# Un_51_old.net
KiCad netlist of a schematic drawn in EAGLE
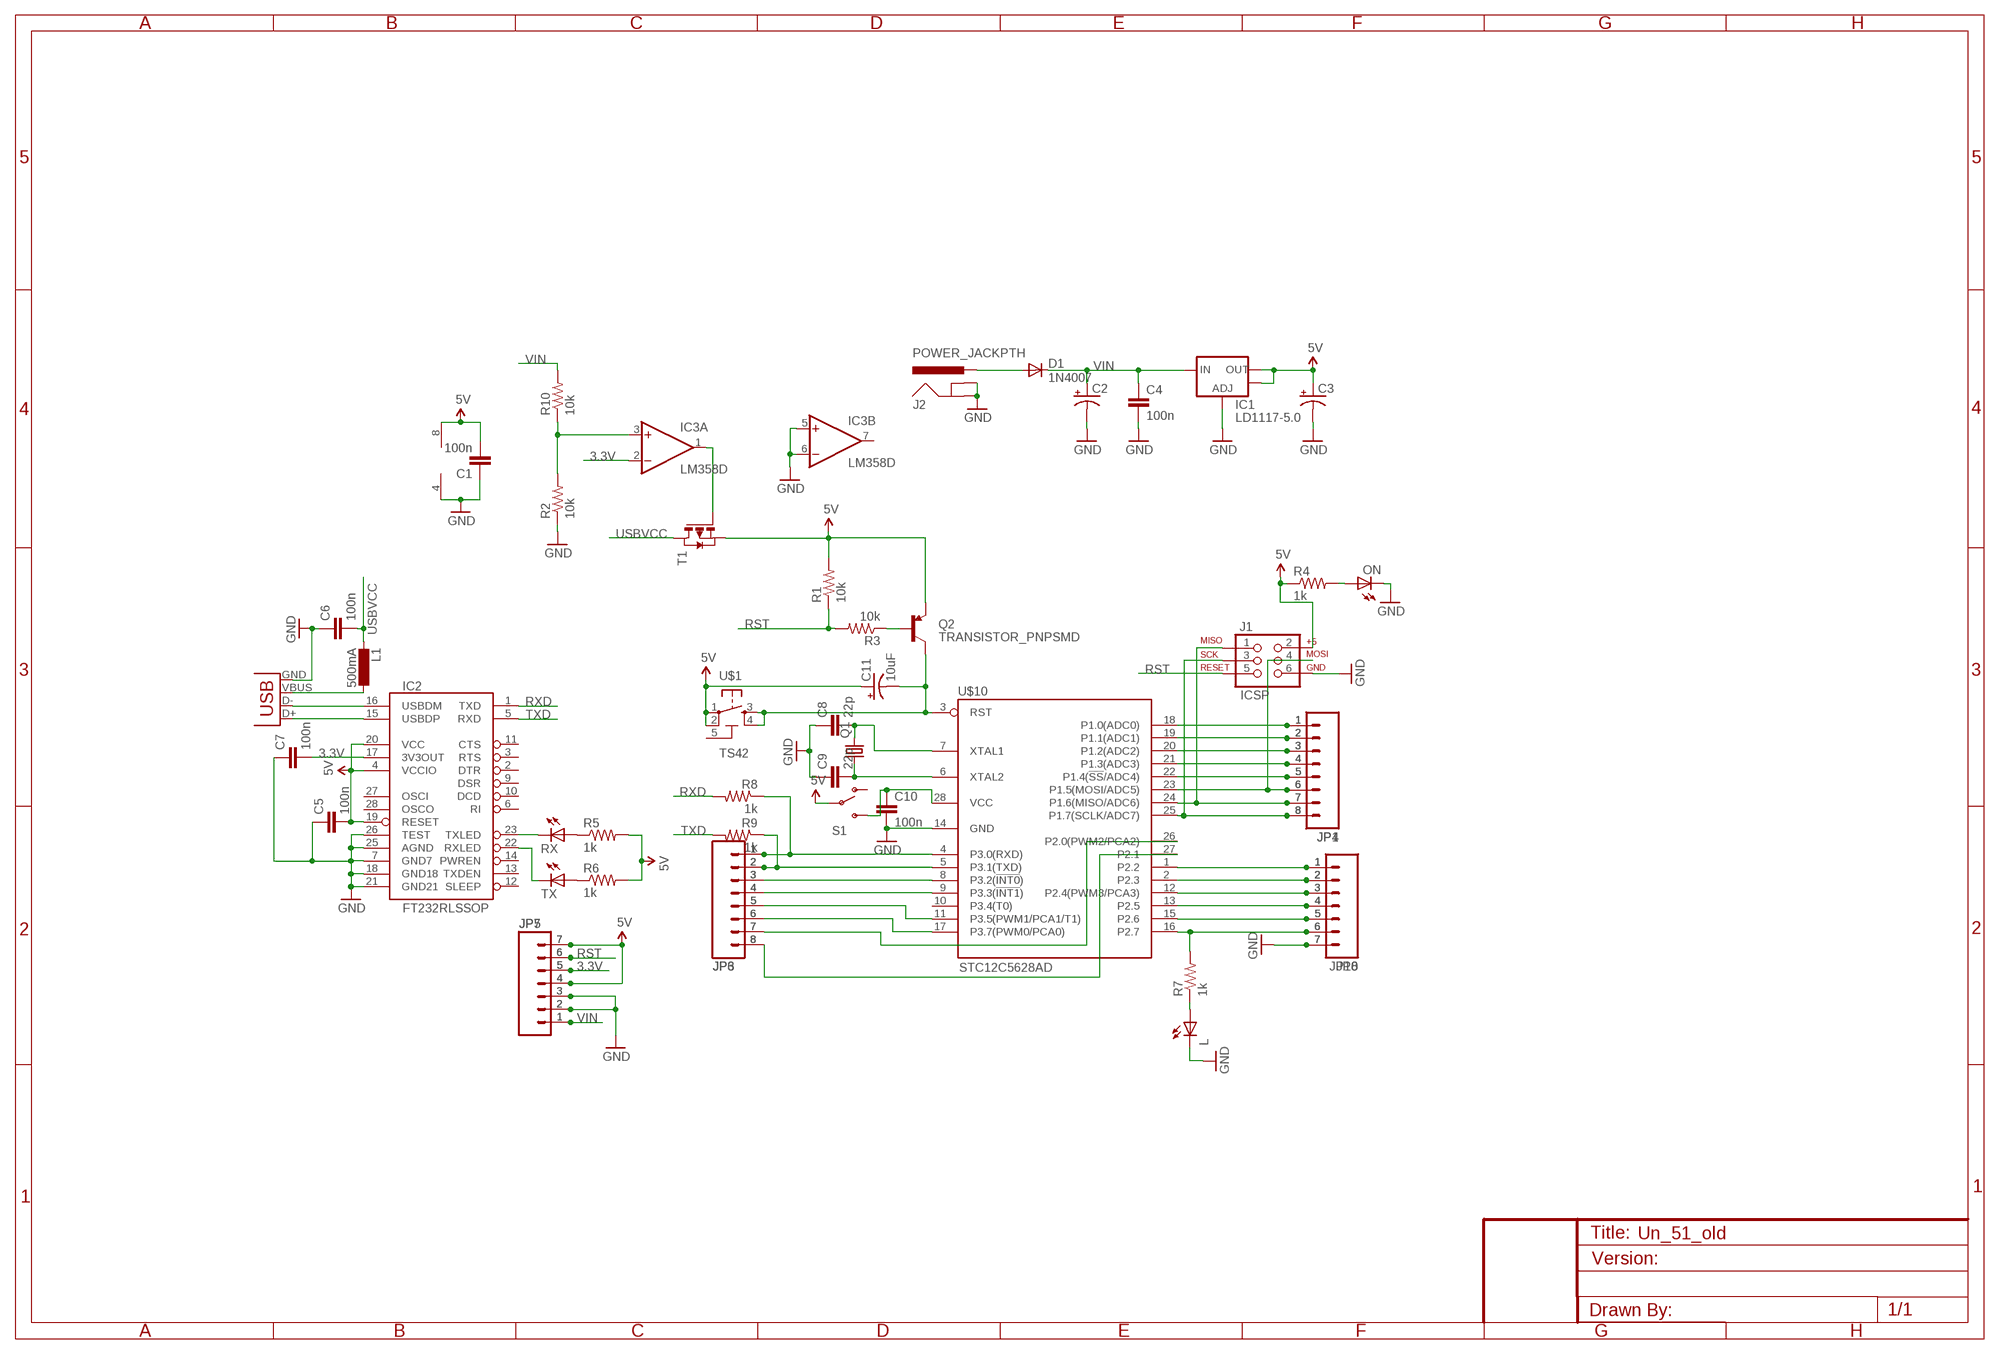
[diagram p0: schematic, sheet 1]

(export (version "E")
  (design (tool "Eeschema 10.0.6"))
  (components
    (comp (ref "C1")
      (value "100n")
      (footprint "eagle-import:0603-CAP")
      (libsource (lib "eagle-import") (part "CAP0603-CAP"))
    )
    (comp (ref "C2")
      (value "CAP_POLD")
      (footprint "eagle-import:PANASONIC_D")
      (libsource (lib "eagle-import") (part "CAP_POLD"))
    )
    (comp (ref "C3")
      (value "CAP_POLD")
      (footprint "eagle-import:PANASONIC_D")
      (libsource (lib "eagle-import") (part "CAP_POLD"))
    )
    (comp (ref "C4")
      (value "100n")
      (footprint "eagle-import:0603-CAP")
      (libsource (lib "eagle-import") (part "CAP0603-CAP"))
    )
    (comp (ref "C5")
      (value "100n")
      (footprint "eagle-import:0603-CAP")
      (libsource (lib "eagle-import") (part "CAP0603-CAP"))
    )
    (comp (ref "C6")
      (value "100n")
      (footprint "eagle-import:0603-CAP")
      (libsource (lib "eagle-import") (part "CAP0603-CAP"))
    )
    (comp (ref "C7")
      (value "100n")
      (footprint "eagle-import:0603-CAP")
      (libsource (lib "eagle-import") (part "CAP0603-CAP"))
    )
    (comp (ref "C8")
      (value "22p")
      (footprint "eagle-import:0805")
      (libsource (lib "eagle-import") (part "CAP0805"))
    )
    (comp (ref "C9")
      (value "22p")
      (footprint "eagle-import:0805")
      (libsource (lib "eagle-import") (part "CAP0805"))
    )
    (comp (ref "C10")
      (value "100n")
      (footprint "eagle-import:0603-CAP")
      (libsource (lib "eagle-import") (part "CAP0603-CAP"))
    )
    (comp (ref "C11")
      (value "10uF")
      (footprint "eagle-import:EIA3216")
      (libsource (lib "eagle-import") (part "CAP_POL1206"))
    )
    (comp (ref "D1")
      (value "1N4007")
      (footprint "eagle-import:SMB")
      (libsource (lib "eagle-import") (part "DIODE-SMB"))
    )
    (comp (ref "IC1")
      (value "LD1117-5.0")
      (footprint "eagle-import:SOT223")
      (libsource (lib "eagle-import") (part "V_REG_LM1117SOT223"))
    )
    (comp (ref "IC2")
      (value "FT232RLSSOP")
      (footprint "eagle-import:SSOP28DB")
      (libsource (lib "eagle-import") (part "FT232RLSSOP"))
    )
    (comp (ref "IC3")
      (value "LM358D")
      (footprint "eagle-import:SO08")
      (libsource (lib "eagle-import") (part "LM358D"))
    )
    (comp (ref "J1")
      (value "ICSP")
      (footprint "eagle-import:2X3")
      (libsource (lib "eagle-import") (part "AVR_SPI_PRG_6PTH"))
    )
    (comp (ref "J2")
      (value "POWER_JACKPTH")
      (footprint "eagle-import:POWER_JACK_PTH")
      (libsource (lib "eagle-import") (part "POWER_JACKPTH"))
    )
    (comp (ref "JP1")
      (value "M081X08")
      (footprint "eagle-import:1X08")
      (libsource (lib "eagle-import") (part "M081X08"))
    )
    (comp (ref "JP3")
      (value "M08")
      (footprint "eagle-import:1X08")
      (libsource (lib "eagle-import") (part "M08"))
    )
    (comp (ref "JP4")
      (value "M081X08")
      (footprint "eagle-import:1X08")
      (libsource (lib "eagle-import") (part "M081X08"))
    )
    (comp (ref "JP5")
      (value "M07")
      (footprint "eagle-import:1X07")
      (libsource (lib "eagle-import") (part "M07"))
    )
    (comp (ref "JP6")
      (value "M08")
      (footprint "eagle-import:1X08")
      (libsource (lib "eagle-import") (part "M08"))
    )
    (comp (ref "JP7")
      (value "M07")
      (footprint "eagle-import:1X07")
      (libsource (lib "eagle-import") (part "M07"))
    )
    (comp (ref "JP8")
      (value "M07")
      (footprint "eagle-import:1X07")
      (libsource (lib "eagle-import") (part "M07"))
    )
    (comp (ref "JP10")
      (value "M07")
      (footprint "eagle-import:1X07")
      (libsource (lib "eagle-import") (part "M07"))
    )
    (comp (ref "L")
      (value "LED0805")
      (footprint "eagle-import:LED-0805")
      (libsource (lib "eagle-import") (part "LED0805"))
    )
    (comp (ref "L1")
      (value "500mA")
      (footprint "eagle-import:L1812")
      (libsource (lib "eagle-import") (part "L-EUL1812"))
    )
    (comp (ref "ON")
      (value "LED0805")
      (footprint "eagle-import:LED-0805")
      (libsource (lib "eagle-import") (part "LED0805"))
    )
    (comp (ref "Q1")
      (value "CRYSTALHC49US")
      (footprint "eagle-import:HC49US")
      (libsource (lib "eagle-import") (part "CRYSTALHC49US"))
    )
    (comp (ref "Q2")
      (value "TRANSISTOR_PNPSMD")
      (footprint "eagle-import:SOT23-3")
      (libsource (lib "eagle-import") (part "TRANSISTOR_PNPSMD"))
    )
    (comp (ref "R1")
      (value "10k")
      (footprint "eagle-import:0805")
      (libsource (lib "eagle-import") (part "RESISTOR0805-RES"))
    )
    (comp (ref "R2")
      (value "10k")
      (footprint "eagle-import:0805")
      (libsource (lib "eagle-import") (part "RESISTOR0805-RES"))
    )
    (comp (ref "R3")
      (value "10k")
      (footprint "eagle-import:0805")
      (libsource (lib "eagle-import") (part "RESISTOR0805-RES"))
    )
    (comp (ref "R4")
      (value "1k")
      (footprint "eagle-import:0805")
      (libsource (lib "eagle-import") (part "RESISTOR0805-RES"))
    )
    (comp (ref "R5")
      (value "1k")
      (footprint "eagle-import:0805")
      (libsource (lib "eagle-import") (part "RESISTOR0805-RES"))
    )
    (comp (ref "R6")
      (value "1k")
      (footprint "eagle-import:0805")
      (libsource (lib "eagle-import") (part "RESISTOR0805-RES"))
    )
    (comp (ref "R7")
      (value "1k")
      (footprint "eagle-import:0805")
      (libsource (lib "eagle-import") (part "RESISTOR0805-RES"))
    )
    (comp (ref "R8")
      (value "1k")
      (footprint "eagle-import:0805")
      (libsource (lib "eagle-import") (part "RESISTOR0805-RES"))
    )
    (comp (ref "R9")
      (value "1k")
      (footprint "eagle-import:0805")
      (libsource (lib "eagle-import") (part "RESISTOR0805-RES"))
    )
    (comp (ref "R10")
      (value "10k")
      (footprint "eagle-import:0805")
      (libsource (lib "eagle-import") (part "RESISTOR0805-RES"))
    )
    (comp (ref "RX")
      (value "LED0805")
      (footprint "eagle-import:LED-0805")
      (libsource (lib "eagle-import") (part "LED0805"))
    )
    (comp (ref "S1")
      (value "SWITCH-SPST")
      (footprint "eagle-import:SWITCH-SPDT2")
      (libsource (lib "eagle-import") (part "SWITCH-SPST"))
    )
    (comp (ref "T1")
      (value "PMOSSOT23")
      (footprint "eagle-import:SOT-23")
      (libsource (lib "eagle-import") (part "PMOSSOT23"))
    )
    (comp (ref "TX")
      (value "LED0805")
      (footprint "eagle-import:LED-0805")
      (libsource (lib "eagle-import") (part "LED0805"))
    )
    (comp (ref "U$1")
      (value "TS42")
      (footprint "eagle-import:TS42")
      (libsource (lib "eagle-import") (part "TS42"))
    )
    (comp (ref "U$10")
      (value "STC12C5628AD")
      (footprint "eagle-import:SO-28W")
      (libsource (lib "eagle-import") (part "STC12C5628AD"))
    )
    (comp (ref "X1")
      (value "USBPTH")
      (footprint "eagle-import:USB-B-PTH")
      (libsource (lib "eagle-import") (part "USBPTH"))
    )
  )
  (nets
    (net (code "1") (name "/3.3V") (class "Default")
      (node (ref "C7") (pin "2") (pinfunction "2_2") (pintype "passive"))
      (node (ref "IC2") (pin "17") (pinfunction "3V3OUT_17") (pintype "output"))
      (node (ref "IC3") (pin "2") (pinfunction "-IN_2") (pintype "input"))
      (node (ref "JP5") (pin "5") (pinfunction "5_5") (pintype "passive"))
      (node (ref "JP7") (pin "5") (pinfunction "5_5") (pintype "passive"))
    )
    (net (code "2") (name "/RST") (class "Default")
      (node (ref "J1") (pin "5") (pinfunction "5_5") (pintype "passive"))
      (node (ref "JP5") (pin "6") (pinfunction "6_6") (pintype "passive"))
      (node (ref "JP7") (pin "6") (pinfunction "6_6") (pintype "passive"))
      (node (ref "R1") (pin "1") (pinfunction "1_1") (pintype "passive"))
      (node (ref "R3") (pin "2") (pinfunction "2_2") (pintype "passive"))
    )
    (net (code "3") (name "/RXD") (class "Default")
      (node (ref "IC2") (pin "1") (pinfunction "TXD_1") (pintype "output"))
      (node (ref "R8") (pin "2") (pinfunction "2_2") (pintype "passive"))
    )
    (net (code "4") (name "/TXD") (class "Default")
      (node (ref "IC2") (pin "5") (pinfunction "RXD_5") (pintype "input"))
      (node (ref "R9") (pin "2") (pinfunction "2_2") (pintype "passive"))
    )
    (net (code "5") (name "/USBVCC") (class "Default")
      (node (ref "C6") (pin "2") (pinfunction "2_2") (pintype "passive"))
      (node (ref "L1") (pin "2") (pinfunction "2_2") (pintype "passive"))
      (node (ref "T1") (pin "1") (pinfunction "D_1") (pintype "passive"))
    )
    (net (code "6") (name "/VIN") (class "Default")
      (node (ref "C2") (pin "+") (pinfunction "+_+") (pintype "passive"))
      (node (ref "C4") (pin "1") (pinfunction "1_1") (pintype "passive"))
      (node (ref "D1") (pin "C") (pinfunction "C_C") (pintype "passive"))
      (node (ref "IC1") (pin "3") (pinfunction "IN_3") (pintype "input"))
      (node (ref "JP5") (pin "1") (pinfunction "1_1") (pintype "passive"))
      (node (ref "JP7") (pin "1") (pinfunction "1_1") (pintype "passive"))
      (node (ref "R10") (pin "2") (pinfunction "2_2") (pintype "passive"))
    )
    (net (code "7") (name "5V") (class "Default")
      (node (ref "C1") (pin "2") (pinfunction "2_2") (pintype "passive"))
      (node (ref "C11") (pin "A") (pinfunction "+_A") (pintype "passive"))
      (node (ref "C3") (pin "+") (pinfunction "+_+") (pintype "passive"))
      (node (ref "C5") (pin "2") (pinfunction "2_2") (pintype "passive"))
      (node (ref "IC1") (pin "2") (pinfunction "OUT_2") (pintype "output"))
      (node (ref "IC1") (pin "4") (pinfunction "OUT_4") (pintype "output"))
      (node (ref "IC2") (pin "19") (pinfunction "RESET_19") (pintype "input"))
      (node (ref "IC2") (pin "20") (pinfunction "VCC_20") (pintype "power_in"))
      (node (ref "IC2") (pin "4") (pinfunction "VCCIO_4") (pintype "power_in"))
      (node (ref "IC3") (pin "8") (pinfunction "V+_8") (pintype "power_in"))
      (node (ref "J1") (pin "2") (pinfunction "2_2") (pintype "passive"))
      (node (ref "JP5") (pin "4") (pinfunction "4_4") (pintype "passive"))
      (node (ref "JP5") (pin "7") (pinfunction "7_7") (pintype "passive"))
      (node (ref "JP7") (pin "4") (pinfunction "4_4") (pintype "passive"))
      (node (ref "JP7") (pin "7") (pinfunction "7_7") (pintype "passive"))
      (node (ref "Q2") (pin "2") (pinfunction "E_2") (pintype "passive"))
      (node (ref "R1") (pin "2") (pinfunction "2_2") (pintype "passive"))
      (node (ref "R4") (pin "1") (pinfunction "1_1") (pintype "passive"))
      (node (ref "R5") (pin "2") (pinfunction "2_2") (pintype "passive"))
      (node (ref "R6") (pin "2") (pinfunction "2_2") (pintype "passive"))
      (node (ref "S1") (pin "2") (pinfunction "P_2") (pintype "passive"))
      (node (ref "T1") (pin "2") (pinfunction "S_2") (pintype "passive"))
      (node (ref "U$1") (pin "1") (pinfunction "1_1") (pintype "passive"))
      (node (ref "U$1") (pin "2") (pinfunction "2_2") (pintype "passive"))
    )
    (net (code "8") (name "GND") (class "Default")
      (node (ref "C1") (pin "1") (pinfunction "1_1") (pintype "passive"))
      (node (ref "C10") (pin "2") (pinfunction "2_2") (pintype "passive"))
      (node (ref "C2") (pin "-") (pinfunction "-_-") (pintype "passive"))
      (node (ref "C3") (pin "-") (pinfunction "-_-") (pintype "passive"))
      (node (ref "C4") (pin "2") (pinfunction "2_2") (pintype "passive"))
      (node (ref "C5") (pin "1") (pinfunction "1_1") (pintype "passive"))
      (node (ref "C6") (pin "1") (pinfunction "1_1") (pintype "passive"))
      (node (ref "C7") (pin "1") (pinfunction "1_1") (pintype "passive"))
      (node (ref "C8") (pin "1") (pinfunction "1_1") (pintype "passive"))
      (node (ref "C9") (pin "1") (pinfunction "1_1") (pintype "passive"))
      (node (ref "IC1") (pin "1") (pinfunction "ADJ_1") (pintype "input"))
      (node (ref "IC2") (pin "18") (pinfunction "GND18_18") (pintype "power_in"))
      (node (ref "IC2") (pin "21") (pinfunction "GND21_21") (pintype "power_in"))
      (node (ref "IC2") (pin "25") (pinfunction "AGND_25") (pintype "power_in"))
      (node (ref "IC2") (pin "26") (pinfunction "TEST_26") (pintype "input"))
      (node (ref "IC2") (pin "7") (pinfunction "GND7_7") (pintype "power_in"))
      (node (ref "IC3") (pin "4") (pinfunction "V-_4") (pintype "power_in"))
      (node (ref "IC3") (pin "5") (pinfunction "+IN_5") (pintype "input"))
      (node (ref "IC3") (pin "6") (pinfunction "-IN_6") (pintype "input"))
      (node (ref "J1") (pin "6") (pinfunction "6_6") (pintype "passive"))
      (node (ref "J2") (pin "GND") (pinfunction "GND_GND") (pintype "bidirectional"))
      (node (ref "J2") (pin "GNDBREAK") (pinfunction "GNDBREAK_GNDBREAK") (pintype "bidirectional"))
      (node (ref "JP10") (pin "7") (pinfunction "7_7") (pintype "passive"))
      (node (ref "JP5") (pin "2") (pinfunction "2_2") (pintype "passive"))
      (node (ref "JP5") (pin "3") (pinfunction "3_3") (pintype "passive"))
      (node (ref "JP7") (pin "2") (pinfunction "2_2") (pintype "passive"))
      (node (ref "JP7") (pin "3") (pinfunction "3_3") (pintype "passive"))
      (node (ref "JP8") (pin "7") (pinfunction "7_7") (pintype "passive"))
      (node (ref "L") (pin "2") (pinfunction "C_2") (pintype "passive"))
      (node (ref "ON") (pin "2") (pinfunction "C_2") (pintype "passive"))
      (node (ref "R2") (pin "1") (pinfunction "1_1") (pintype "passive"))
      (node (ref "U$10") (pin "14") (pinfunction "GND_14") (pintype "bidirectional"))
      (node (ref "X1") (pin "GND") (pinfunction "GND_GND") (pintype "bidirectional"))
    )
    (net (code "9") (name "Net-(C11--)") (class "Default")
      (node (ref "C11") (pin "C") (pinfunction "-_C") (pintype "passive"))
      (node (ref "Q2") (pin "3") (pinfunction "C_3") (pintype "passive"))
      (node (ref "U$1") (pin "3") (pinfunction "3_3") (pintype "passive"))
      (node (ref "U$1") (pin "4") (pinfunction "4_4") (pintype "passive"))
      (node (ref "U$10") (pin "3") (pinfunction "RST_3") (pintype "bidirectional"))
    )
    (net (code "10") (name "Net-(D1-PadA)") (class "Default")
      (node (ref "D1") (pin "A") (pinfunction "A_A") (pintype "passive"))
      (node (ref "J2") (pin "PWR") (pinfunction "PWR_PWR") (pintype "bidirectional"))
    )
    (net (code "11") (name "Net-(IC2-RXLED)") (class "Default")
      (node (ref "IC2") (pin "22") (pinfunction "RXLED_22") (pintype "input"))
      (node (ref "TX") (pin "2") (pinfunction "C_2") (pintype "passive"))
    )
    (net (code "12") (name "Net-(IC2-TXLED)") (class "Default")
      (node (ref "IC2") (pin "23") (pinfunction "TXLED_23") (pintype "input"))
      (node (ref "RX") (pin "2") (pinfunction "C_2") (pintype "passive"))
    )
    (net (code "13") (name "Net-(IC2-USBDM)") (class "Default")
      (node (ref "IC2") (pin "16") (pinfunction "USBDM_16") (pintype "bidirectional"))
      (node (ref "X1") (pin "D-") (pinfunction "D-_D-") (pintype "bidirectional"))
    )
    (net (code "14") (name "Net-(IC2-USBDP)") (class "Default")
      (node (ref "IC2") (pin "15") (pinfunction "USBDP_15") (pintype "bidirectional"))
      (node (ref "X1") (pin "D+") (pinfunction "D+_D+") (pintype "bidirectional"))
    )
    (net (code "15") (name "Net-(IC3A-+IN)") (class "Default")
      (node (ref "IC3") (pin "3") (pinfunction "+IN_3") (pintype "input"))
      (node (ref "R10") (pin "1") (pinfunction "1_1") (pintype "passive"))
      (node (ref "R2") (pin "2") (pinfunction "2_2") (pintype "passive"))
    )
    (net (code "16") (name "Net-(IC3A-OUT)") (class "Default")
      (node (ref "IC3") (pin "1") (pinfunction "OUT_1") (pintype "output"))
      (node (ref "T1") (pin "3") (pinfunction "G_3") (pintype "passive"))
    )
    (net (code "17") (name "Net-(L-A)") (class "Default")
      (node (ref "L") (pin "1") (pinfunction "A_1") (pintype "passive"))
      (node (ref "R7") (pin "1") (pinfunction "1_1") (pintype "passive"))
    )
    (net (code "18") (name "Net-(L1-Pad1)") (class "Default")
      (node (ref "L1") (pin "1") (pinfunction "1_1") (pintype "passive"))
      (node (ref "X1") (pin "VBUS") (pinfunction "VBUS_VBUS") (pintype "bidirectional"))
    )
    (net (code "19") (name "Net-(ON-A)") (class "Default")
      (node (ref "ON") (pin "1") (pinfunction "A_1") (pintype "passive"))
      (node (ref "R4") (pin "2") (pinfunction "2_2") (pintype "passive"))
    )
    (net (code "20") (name "Net-(Q2-B)") (class "Default")
      (node (ref "Q2") (pin "1") (pinfunction "B_1") (pintype "passive"))
      (node (ref "R3") (pin "1") (pinfunction "1_1") (pintype "passive"))
    )
    (net (code "21") (name "Net-(RX-A)") (class "Default")
      (node (ref "R5") (pin "1") (pinfunction "1_1") (pintype "passive"))
      (node (ref "RX") (pin "1") (pinfunction "A_1") (pintype "passive"))
    )
    (net (code "22") (name "Net-(S1-S)") (class "Default")
      (node (ref "C10") (pin "1") (pinfunction "1_1") (pintype "passive"))
      (node (ref "S1") (pin "3") (pinfunction "S_3") (pintype "passive"))
      (node (ref "U$10") (pin "28") (pinfunction "VCC_28") (pintype "bidirectional"))
    )
    (net (code "23") (name "Net-(TX-A)") (class "Default")
      (node (ref "R6") (pin "1") (pinfunction "1_1") (pintype "passive"))
      (node (ref "TX") (pin "1") (pinfunction "A_1") (pintype "passive"))
    )
    (net (code "24") (name "Net-(U$10-P1.0(ADC0))") (class "Default")
      (node (ref "JP1") (pin "1") (pinfunction "1_1") (pintype "passive"))
      (node (ref "JP4") (pin "1") (pinfunction "1_1") (pintype "passive"))
      (node (ref "U$10") (pin "18") (pinfunction "P1.0(ADC0)_18") (pintype "bidirectional"))
    )
    (net (code "25") (name "Net-(U$10-P1.1(ADC1))") (class "Default")
      (node (ref "JP1") (pin "2") (pinfunction "2_2") (pintype "passive"))
      (node (ref "JP4") (pin "2") (pinfunction "2_2") (pintype "passive"))
      (node (ref "U$10") (pin "19") (pinfunction "P1.1(ADC1)_19") (pintype "bidirectional"))
    )
    (net (code "26") (name "Net-(U$10-P1.2(ADC2))") (class "Default")
      (node (ref "JP1") (pin "3") (pinfunction "3_3") (pintype "passive"))
      (node (ref "JP4") (pin "3") (pinfunction "3_3") (pintype "passive"))
      (node (ref "U$10") (pin "20") (pinfunction "P1.2(ADC2)_20") (pintype "bidirectional"))
    )
    (net (code "27") (name "Net-(U$10-P1.3(ADC3))") (class "Default")
      (node (ref "JP1") (pin "4") (pinfunction "4_4") (pintype "passive"))
      (node (ref "JP4") (pin "4") (pinfunction "4_4") (pintype "passive"))
      (node (ref "U$10") (pin "21") (pinfunction "P1.3(ADC3)_21") (pintype "bidirectional"))
    )
    (net (code "28") (name "Net-(U$10-P1.4(~{SS}{slash}ADC4))") (class "Default")
      (node (ref "JP1") (pin "5") (pinfunction "5_5") (pintype "passive"))
      (node (ref "JP4") (pin "5") (pinfunction "5_5") (pintype "passive"))
      (node (ref "U$10") (pin "22") (pinfunction "P1.4(~{SS}/ADC4)_22") (pintype "bidirectional"))
    )
    (net (code "29") (name "Net-(U$10-P1.5(MOSI{slash}ADC5))") (class "Default")
      (node (ref "J1") (pin "4") (pinfunction "4_4") (pintype "passive"))
      (node (ref "JP1") (pin "6") (pinfunction "6_6") (pintype "passive"))
      (node (ref "JP4") (pin "6") (pinfunction "6_6") (pintype "passive"))
      (node (ref "U$10") (pin "23") (pinfunction "P1.5(MOSI/ADC5)_23") (pintype "bidirectional"))
    )
    (net (code "30") (name "Net-(U$10-P1.6(MISO{slash}ADC6))") (class "Default")
      (node (ref "J1") (pin "1") (pinfunction "1_1") (pintype "passive"))
      (node (ref "JP1") (pin "7") (pinfunction "7_7") (pintype "passive"))
      (node (ref "JP4") (pin "7") (pinfunction "7_7") (pintype "passive"))
      (node (ref "U$10") (pin "24") (pinfunction "P1.6(MISO/ADC6)_24") (pintype "bidirectional"))
    )
    (net (code "31") (name "Net-(U$10-P1.7(SCLK{slash}ADC7))") (class "Default")
      (node (ref "J1") (pin "3") (pinfunction "3_3") (pintype "passive"))
      (node (ref "JP1") (pin "8") (pinfunction "8_8") (pintype "passive"))
      (node (ref "JP4") (pin "8") (pinfunction "8_8") (pintype "passive"))
      (node (ref "U$10") (pin "25") (pinfunction "P1.7(SCLK/ADC7)_25") (pintype "bidirectional"))
    )
    (net (code "32") (name "Net-(U$10-P2.0(PWM2{slash}PCA2))") (class "Default")
      (node (ref "JP3") (pin "7") (pinfunction "7_7") (pintype "passive"))
      (node (ref "JP6") (pin "7") (pinfunction "7_7") (pintype "passive"))
      (node (ref "U$10") (pin "26") (pinfunction "P2.0(PWM2/PCA2)_26") (pintype "bidirectional"))
    )
    (net (code "33") (name "Net-(U$10-P2.1)") (class "Default")
      (node (ref "JP3") (pin "8") (pinfunction "8_8") (pintype "passive"))
      (node (ref "JP6") (pin "8") (pinfunction "8_8") (pintype "passive"))
      (node (ref "U$10") (pin "27") (pinfunction "P2.1_27") (pintype "bidirectional"))
    )
    (net (code "34") (name "Net-(U$10-P2.2)") (class "Default")
      (node (ref "JP10") (pin "1") (pinfunction "1_1") (pintype "passive"))
      (node (ref "JP8") (pin "1") (pinfunction "1_1") (pintype "passive"))
      (node (ref "U$10") (pin "1") (pinfunction "P2.2_1") (pintype "bidirectional"))
    )
    (net (code "35") (name "Net-(U$10-P2.3)") (class "Default")
      (node (ref "JP10") (pin "2") (pinfunction "2_2") (pintype "passive"))
      (node (ref "JP8") (pin "2") (pinfunction "2_2") (pintype "passive"))
      (node (ref "U$10") (pin "2") (pinfunction "P2.3_2") (pintype "bidirectional"))
    )
    (net (code "36") (name "Net-(U$10-P2.4(PWM3{slash}PCA3))") (class "Default")
      (node (ref "JP10") (pin "3") (pinfunction "3_3") (pintype "passive"))
      (node (ref "JP8") (pin "3") (pinfunction "3_3") (pintype "passive"))
      (node (ref "U$10") (pin "12") (pinfunction "P2.4(PWM3/PCA3)_12") (pintype "bidirectional"))
    )
    (net (code "37") (name "Net-(U$10-P2.5)") (class "Default")
      (node (ref "JP10") (pin "4") (pinfunction "4_4") (pintype "passive"))
      (node (ref "JP8") (pin "4") (pinfunction "4_4") (pintype "passive"))
      (node (ref "U$10") (pin "13") (pinfunction "P2.5_13") (pintype "bidirectional"))
    )
    (net (code "38") (name "Net-(U$10-P2.6)") (class "Default")
      (node (ref "JP10") (pin "5") (pinfunction "5_5") (pintype "passive"))
      (node (ref "JP8") (pin "5") (pinfunction "5_5") (pintype "passive"))
      (node (ref "U$10") (pin "15") (pinfunction "P2.6_15") (pintype "bidirectional"))
    )
    (net (code "39") (name "Net-(U$10-P2.7)") (class "Default")
      (node (ref "JP10") (pin "6") (pinfunction "6_6") (pintype "passive"))
      (node (ref "JP8") (pin "6") (pinfunction "6_6") (pintype "passive"))
      (node (ref "R7") (pin "2") (pinfunction "2_2") (pintype "passive"))
      (node (ref "U$10") (pin "16") (pinfunction "P2.7_16") (pintype "bidirectional"))
    )
    (net (code "40") (name "Net-(U$10-P3.0(RXD))") (class "Default")
      (node (ref "JP3") (pin "1") (pinfunction "1_1") (pintype "passive"))
      (node (ref "JP6") (pin "1") (pinfunction "1_1") (pintype "passive"))
      (node (ref "R8") (pin "1") (pinfunction "1_1") (pintype "passive"))
      (node (ref "U$10") (pin "4") (pinfunction "P3.0(RXD)_4") (pintype "bidirectional"))
    )
    (net (code "41") (name "Net-(U$10-P3.1(TXD))") (class "Default")
      (node (ref "JP3") (pin "2") (pinfunction "2_2") (pintype "passive"))
      (node (ref "JP6") (pin "2") (pinfunction "2_2") (pintype "passive"))
      (node (ref "R9") (pin "1") (pinfunction "1_1") (pintype "passive"))
      (node (ref "U$10") (pin "5") (pinfunction "P3.1(TXD)_5") (pintype "bidirectional"))
    )
    (net (code "42") (name "Net-(U$10-P3.2(~{INT0}))") (class "Default")
      (node (ref "JP3") (pin "3") (pinfunction "3_3") (pintype "passive"))
      (node (ref "JP6") (pin "3") (pinfunction "3_3") (pintype "passive"))
      (node (ref "U$10") (pin "8") (pinfunction "P3.2(~{INT0})_8") (pintype "bidirectional"))
    )
    (net (code "43") (name "Net-(U$10-P3.3(~{INT1}))") (class "Default")
      (node (ref "JP3") (pin "4") (pinfunction "4_4") (pintype "passive"))
      (node (ref "JP6") (pin "4") (pinfunction "4_4") (pintype "passive"))
      (node (ref "U$10") (pin "9") (pinfunction "P3.3(~{INT1})_9") (pintype "bidirectional"))
    )
    (net (code "44") (name "Net-(U$10-P3.5(PWM1{slash}PCA1{slash}T1))") (class "Default")
      (node (ref "JP3") (pin "5") (pinfunction "5_5") (pintype "passive"))
      (node (ref "JP6") (pin "5") (pinfunction "5_5") (pintype "passive"))
      (node (ref "U$10") (pin "11") (pinfunction "P3.5(PWM1/PCA1/T1)_11") (pintype "bidirectional"))
    )
    (net (code "45") (name "Net-(U$10-P3.7(PWM0{slash}PCA0))") (class "Default")
      (node (ref "JP3") (pin "6") (pinfunction "6_6") (pintype "passive"))
      (node (ref "JP6") (pin "6") (pinfunction "6_6") (pintype "passive"))
      (node (ref "U$10") (pin "17") (pinfunction "P3.7(PWM0/PCA0)_17") (pintype "bidirectional"))
    )
    (net (code "46") (name "Net-(U$10-XTAL1)") (class "Default")
      (node (ref "C8") (pin "2") (pinfunction "2_2") (pintype "passive"))
      (node (ref "Q1") (pin "2") (pinfunction "2_2") (pintype "passive"))
      (node (ref "U$10") (pin "7") (pinfunction "XTAL1_7") (pintype "bidirectional"))
    )
    (net (code "47") (name "Net-(U$10-XTAL2)") (class "Default")
      (node (ref "C9") (pin "2") (pinfunction "2_2") (pintype "passive"))
      (node (ref "Q1") (pin "1") (pinfunction "1_1") (pintype "passive"))
      (node (ref "U$10") (pin "6") (pinfunction "XTAL2_6") (pintype "bidirectional"))
    )
    (net (code "48") (name "unconnected-(IC2-CTS-Pad11)") (class "Default")
      (node (ref "IC2") (pin "11") (pinfunction "CTS_11") (pintype "input"))
    )
    (net (code "49") (name "unconnected-(IC2-DCD-Pad10)") (class "Default")
      (node (ref "IC2") (pin "10") (pinfunction "DCD_10") (pintype "input"))
    )
    (net (code "50") (name "unconnected-(IC2-DSR-Pad9)") (class "Default")
      (node (ref "IC2") (pin "9") (pinfunction "DSR_9") (pintype "input"))
    )
    (net (code "51") (name "unconnected-(IC2-DTR-Pad2)") (class "Default")
      (node (ref "IC2") (pin "2") (pinfunction "DTR_2") (pintype "output"))
    )
    (net (code "52") (name "unconnected-(IC2-OSCI-Pad27)") (class "Default")
      (node (ref "IC2") (pin "27") (pinfunction "OSCI_27") (pintype "input"))
    )
    (net (code "53") (name "unconnected-(IC2-OSCO-Pad28)") (class "Default")
      (node (ref "IC2") (pin "28") (pinfunction "OSCO_28") (pintype "output"))
    )
    (net (code "54") (name "unconnected-(IC2-PWREN-Pad14)") (class "Default")
      (node (ref "IC2") (pin "14") (pinfunction "PWREN_14") (pintype "input"))
    )
    (net (code "55") (name "unconnected-(IC2-RI-Pad6)") (class "Default")
      (node (ref "IC2") (pin "6") (pinfunction "RI_6") (pintype "input"))
    )
    (net (code "56") (name "unconnected-(IC2-RTS-Pad3)") (class "Default")
      (node (ref "IC2") (pin "3") (pinfunction "RTS_3") (pintype "output"))
    )
    (net (code "57") (name "unconnected-(IC2-SLEEP-Pad12)") (class "Default")
      (node (ref "IC2") (pin "12") (pinfunction "SLEEP_12") (pintype "input"))
    )
    (net (code "58") (name "unconnected-(IC2-TXDEN-Pad13)") (class "Default")
      (node (ref "IC2") (pin "13") (pinfunction "TXDEN_13") (pintype "input"))
    )
    (net (code "59") (name "unconnected-(IC3B-OUT-Pad7)") (class "Default")
      (node (ref "IC3") (pin "7") (pinfunction "OUT_7") (pintype "output"))
    )
    (net (code "60") (name "unconnected-(S1-O-Pad1)") (class "Default")
      (node (ref "S1") (pin "1") (pinfunction "O_1") (pintype "passive"))
    )
    (net (code "61") (name "unconnected-(U$1-Pad5)") (class "Default")
      (node (ref "U$1") (pin "5") (pinfunction "5_5") (pintype "passive"))
    )
    (net (code "62") (name "unconnected-(U$10-P3.4(T0)-Pad10)") (class "Default")
      (node (ref "U$10") (pin "10") (pinfunction "P3.4(T0)_10") (pintype "bidirectional"))
    )
  )
)
